# 1_P1.net
KiCad netlist of a schematic drawn in Altium Designer
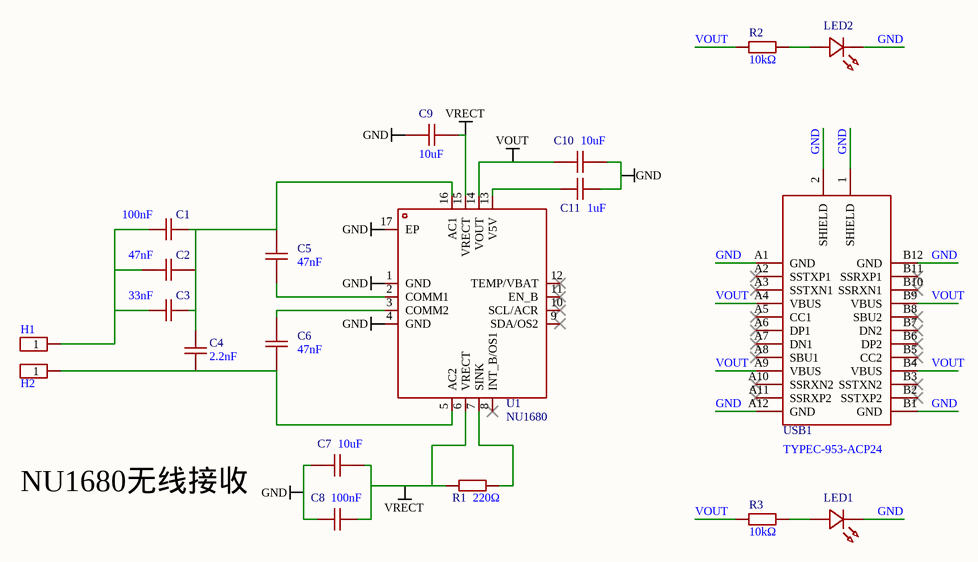
[diagram p0: 1_P1.schdoc]

(export (version "E")
  (design (tool "Eeschema 10.0.6"))
  (components
    (comp (ref "C1")
      (value "100nF")
      (footprint "C0603")
      (fields
        (field (name "MANUFACTURER") "FH(风华)")
        (field (name "MANUFACTURER PART") "0603B104K500NT")
        (field (name "TOLERANCE") "±10%")
      )
      (libsource (lib "altium-import") (part "root_0_0603B104K500NT_"))
    )
    (comp (ref "C2")
      (value "47nF")
      (footprint "C0603")
      (fields
        (field (name "MANUFACTURER") "FH(风华)")
        (field (name "MANUFACTURER PART") "0603B473K500NT")
        (field (name "TOLERANCE") "±10%")
      )
      (libsource (lib "altium-import") (part "root_1_0603B473K500NT_"))
    )
    (comp (ref "C3")
      (value "33nF")
      (footprint "C0603")
      (fields
        (field (name "MANUFACTURER") "SAMSUNG(三星)")
        (field (name "MANUFACTURER PART") "CL10B333KB8NNNC")
        (field (name "TOLERANCE") "±10%")
      )
      (libsource (lib "altium-import") (part "root_0_CL10B333KB8NNNC_"))
    )
    (comp (ref "C4")
      (value "2.2nF")
      (footprint "C0603")
      (fields
        (field (name "MANUFACTURER") "FH(风华)")
        (field (name "MANUFACTURER PART") "0603B222K500NT")
        (field (name "TOLERANCE") "±10%")
      )
      (libsource (lib "altium-import") (part "root_1_0603B222K500NT_"))
    )
    (comp (ref "C5")
      (value "47nF")
      (footprint "C0603")
      (fields
        (field (name "MANUFACTURER") "FH(风华)")
        (field (name "MANUFACTURER PART") "0603B473K500NT")
        (field (name "TOLERANCE") "±10%")
      )
      (libsource (lib "altium-import") (part "root_2_0603B473K500NT_"))
    )
    (comp (ref "C6")
      (value "47nF")
      (footprint "C0603")
      (fields
        (field (name "MANUFACTURER") "FH(风华)")
        (field (name "MANUFACTURER PART") "0603B473K500NT")
        (field (name "TOLERANCE") "±10%")
      )
      (libsource (lib "altium-import") (part "root_2_0603B473K500NT_"))
    )
    (comp (ref "C7")
      (value "10uF")
      (footprint "C0603")
      (fields
        (field (name "MANUFACTURER") "SAMSUNG(三星)")
        (field (name "MANUFACTURER PART") "CL10A106MA8NRNC")
        (field (name "TOLERANCE") "±20%")
      )
      (libsource (lib "altium-import") (part "root_0_CL10A106MA8NRNC_"))
    )
    (comp (ref "C8")
      (value "100nF")
      (footprint "C0603")
      (fields
        (field (name "MANUFACTURER") "FH(风华)")
        (field (name "MANUFACTURER PART") "0603B104K500NT")
        (field (name "TOLERANCE") "±10%")
      )
      (libsource (lib "altium-import") (part "root_0_0603B104K500NT_"))
    )
    (comp (ref "C9")
      (value "10uF")
      (footprint "C0603")
      (fields
        (field (name "MANUFACTURER") "SAMSUNG(三星)")
        (field (name "MANUFACTURER PART") "CL10A106MA8NRNC")
        (field (name "TOLERANCE") "±20%")
      )
      (libsource (lib "altium-import") (part "root_0_CL10A106MA8NRNC_"))
    )
    (comp (ref "C10")
      (value "10uF")
      (footprint "C0603")
      (fields
        (field (name "MANUFACTURER") "SAMSUNG(三星)")
        (field (name "MANUFACTURER PART") "CL10A106MA8NRNC")
        (field (name "TOLERANCE") "±20%")
      )
      (libsource (lib "altium-import") (part "root_0_CL10A106MA8NRNC_"))
    )
    (comp (ref "C11")
      (value "1uF")
      (footprint "C0603")
      (fields
        (field (name "MANUFACTURER PART") "CL10A105KB8NNNC")
        (field (name "MANUFACTURER") "SAMSUNG(三星)")
        (field (name "TOLERANCE") "±10%")
      )
      (libsource (lib "altium-import") (part "root_0_CL10A105KB8NNNC_"))
    )
    (comp (ref "H1")
      (value "2.54-1*1P针")
      (footprint "2mm-1.3mm孔")
      (fields (field (name "MANUFACTURER") "BOOMELE(博穆精密)"))
      (libsource (lib "altium-import") (part "root_2_2.54-1*1P针_"))
    )
    (comp (ref "H2")
      (value "2.54-1*1P针")
      (footprint "2mm-1.3mm孔")
      (fields (field (name "MANUFACTURER") "BOOMELE(博穆精密)"))
      (libsource (lib "altium-import") (part "root_2_2.54-1*1P针_"))
    )
    (comp (ref "LED1")
      (value "MHT192DUGCT")
      (footprint "LED0603-RD")
      (fields (field (name "MANUFACTURER") "MEIHUA(美华)"))
      (libsource (lib "altium-import") (part "root_2_MHT192DUGCT_"))
    )
    (comp (ref "LED2")
      (value "MHT192DUGCT")
      (footprint "LED0603-RD")
      (fields (field (name "MANUFACTURER") "MEIHUA(美华)"))
      (libsource (lib "altium-import") (part "root_2_MHT192DUGCT_"))
    )
    (comp (ref "R1")
      (value "220Ω")
      (footprint "R0805")
      (fields
        (field (name "MANUFACTURER") "UNI-ROYAL(厚声)")
        (field (name "MANUFACTURER PART") "0805W8J0221T5E")
        (field (name "TOLERANCE") "±5%")
      )
      (libsource (lib "altium-import") (part "root_0_0805W8J0221T5E_"))
    )
    (comp (ref "R2")
      (value "10kΩ")
      (footprint "R0603")
      (fields
        (field (name "MANUFACTURER") "UNI-ROYAL(厚声)")
        (field (name "MANUFACTURER PART") "0603WAF1002T5E")
        (field (name "TOLERANCE") "±1%")
      )
      (libsource (lib "altium-import") (part "root_0_0603WAF1002T5E_"))
    )
    (comp (ref "R3")
      (value "10kΩ")
      (footprint "R0603")
      (fields
        (field (name "MANUFACTURER") "UNI-ROYAL(厚声)")
        (field (name "MANUFACTURER PART") "0603WAF1002T5E")
        (field (name "TOLERANCE") "±1%")
      )
      (libsource (lib "altium-import") (part "root_0_0603WAF1002T5E_"))
    )
    (comp (ref "U1")
      (value "NU1680")
      (footprint "QFN-16_L3.0-W3.0-P0.50-TL-EP1.9")
      (fields (field (name "DEVICE") "NU1680"))
      (libsource (lib "altium-import") (part "root_0_NU1680_"))
    )
    (comp (ref "USB1")
      (value "TYPEC-953-ACP24")
      (footprint "USB-C-SMD_TYPEC-953-ACP24")
      (fields (field (name "MANUFACTURER") "XUNPU(讯普)"))
      (libsource (lib "altium-import") (part "root_0_TYPEC-953-ACP24_"))
    )
  )
  (nets
    (net (code "1") (name "GND") (class "Default")
      (node (ref "C10") (pin "2") (pinfunction "2_2") (pintype "passive"))
      (node (ref "C11") (pin "2") (pinfunction "2_2") (pintype "passive"))
      (node (ref "C7") (pin "1") (pinfunction "1_1") (pintype "passive"))
      (node (ref "C8") (pin "1") (pinfunction "1_1") (pintype "passive"))
      (node (ref "C9") (pin "1") (pinfunction "1_1") (pintype "passive"))
      (node (ref "LED1") (pin "1") (pinfunction "K_1") (pintype "passive"))
      (node (ref "LED2") (pin "1") (pinfunction "K_1") (pintype "passive"))
      (node (ref "U1") (pin "1") (pinfunction "GND_1") (pintype "passive"))
      (node (ref "U1") (pin "17") (pinfunction "EP_17") (pintype "passive"))
      (node (ref "U1") (pin "4") (pinfunction "GND_4") (pintype "passive"))
      (node (ref "USB1") (pin "1") (pinfunction "SHIELD_1") (pintype "passive"))
      (node (ref "USB1") (pin "2") (pinfunction "SHIELD_2") (pintype "passive"))
      (node (ref "USB1") (pin "A1") (pinfunction "GND_A1") (pintype "passive"))
      (node (ref "USB1") (pin "A12") (pinfunction "GND_A12") (pintype "passive"))
      (node (ref "USB1") (pin "B1") (pinfunction "GND_B1") (pintype "passive"))
      (node (ref "USB1") (pin "B12") (pinfunction "GND_B12") (pintype "passive"))
    )
    (net (code "2") (name "Net-(C1-Pad1)") (class "Default")
      (node (ref "C1") (pin "1") (pinfunction "1_1") (pintype "passive"))
      (node (ref "C2") (pin "2") (pinfunction "2_2") (pintype "passive"))
      (node (ref "C3") (pin "1") (pinfunction "1_1") (pintype "passive"))
      (node (ref "H1") (pin "1") (pinfunction "1_1") (pintype "passive"))
    )
    (net (code "3") (name "Net-(LED1-A)") (class "Default")
      (node (ref "LED1") (pin "2") (pinfunction "A_2") (pintype "passive"))
      (node (ref "R3") (pin "2") (pinfunction "2_2") (pintype "passive"))
    )
    (net (code "4") (name "Net-(LED2-A)") (class "Default")
      (node (ref "LED2") (pin "2") (pinfunction "A_2") (pintype "passive"))
      (node (ref "R2") (pin "2") (pinfunction "2_2") (pintype "passive"))
    )
    (net (code "5") (name "Net-(U1-AC1)") (class "Default")
      (node (ref "C1") (pin "2") (pinfunction "2_2") (pintype "passive"))
      (node (ref "C2") (pin "1") (pinfunction "1_1") (pintype "passive"))
      (node (ref "C3") (pin "2") (pinfunction "2_2") (pintype "passive"))
      (node (ref "C4") (pin "2") (pinfunction "2_2") (pintype "passive"))
      (node (ref "C5") (pin "1") (pinfunction "1_1") (pintype "passive"))
      (node (ref "U1") (pin "16") (pinfunction "AC1_16") (pintype "passive"))
    )
    (net (code "6") (name "Net-(U1-AC2)") (class "Default")
      (node (ref "C4") (pin "1") (pinfunction "1_1") (pintype "passive"))
      (node (ref "C6") (pin "2") (pinfunction "2_2") (pintype "passive"))
      (node (ref "H2") (pin "1") (pinfunction "1_1") (pintype "passive"))
      (node (ref "U1") (pin "5") (pinfunction "AC2_5") (pintype "passive"))
    )
    (net (code "7") (name "Net-(U1-COMM1)") (class "Default")
      (node (ref "C5") (pin "2") (pinfunction "2_2") (pintype "passive"))
      (node (ref "U1") (pin "2") (pinfunction "COMM1_2") (pintype "passive"))
    )
    (net (code "8") (name "Net-(U1-COMM2)") (class "Default")
      (node (ref "C6") (pin "1") (pinfunction "1_1") (pintype "passive"))
      (node (ref "U1") (pin "3") (pinfunction "COMM2_3") (pintype "passive"))
    )
    (net (code "9") (name "Net-(U1-SINK)") (class "Default")
      (node (ref "R1") (pin "2") (pinfunction "2_2") (pintype "passive"))
      (node (ref "U1") (pin "7") (pinfunction "SINK_7") (pintype "passive"))
    )
    (net (code "10") (name "Net-(U1-V5V)") (class "Default")
      (node (ref "C11") (pin "1") (pinfunction "1_1") (pintype "passive"))
      (node (ref "U1") (pin "13") (pinfunction "V5V_13") (pintype "passive"))
    )
    (net (code "11") (name "VOUT") (class "Default")
      (node (ref "C10") (pin "1") (pinfunction "1_1") (pintype "passive"))
      (node (ref "R2") (pin "1") (pinfunction "1_1") (pintype "passive"))
      (node (ref "R3") (pin "1") (pinfunction "1_1") (pintype "passive"))
      (node (ref "U1") (pin "14") (pinfunction "VOUT_14") (pintype "passive"))
      (node (ref "USB1") (pin "A4") (pinfunction "VBUS_A4") (pintype "passive"))
      (node (ref "USB1") (pin "A9") (pinfunction "VBUS_A9") (pintype "passive"))
      (node (ref "USB1") (pin "B4") (pinfunction "VBUS_B4") (pintype "passive"))
      (node (ref "USB1") (pin "B9") (pinfunction "VBUS_B9") (pintype "passive"))
    )
    (net (code "12") (name "VRECT") (class "Default")
      (node (ref "C7") (pin "2") (pinfunction "2_2") (pintype "passive"))
      (node (ref "C8") (pin "2") (pinfunction "2_2") (pintype "passive"))
      (node (ref "C9") (pin "2") (pinfunction "2_2") (pintype "passive"))
      (node (ref "R1") (pin "1") (pinfunction "1_1") (pintype "passive"))
      (node (ref "U1") (pin "15") (pinfunction "VRECT_15") (pintype "passive"))
      (node (ref "U1") (pin "6") (pinfunction "VRECT_6") (pintype "passive"))
    )
    (net (code "13") (name "unconnected-(U1-EN_B-Pad11)") (class "Default")
      (node (ref "U1") (pin "11") (pinfunction "EN_B_11") (pintype "passive+no_connect"))
    )
    (net (code "14") (name "unconnected-(U1-INT_B{slash}OS1-Pad8)") (class "Default")
      (node (ref "U1") (pin "8") (pinfunction "INT_B/OS1_8") (pintype "passive+no_connect"))
    )
    (net (code "15") (name "unconnected-(U1-SCL{slash}ACR-Pad10)") (class "Default")
      (node (ref "U1") (pin "10") (pinfunction "SCL/ACR_10") (pintype "passive+no_connect"))
    )
    (net (code "16") (name "unconnected-(U1-SDA{slash}OS2-Pad9)") (class "Default")
      (node (ref "U1") (pin "9") (pinfunction "SDA/OS2_9") (pintype "passive+no_connect"))
    )
    (net (code "17") (name "unconnected-(U1-TEMP{slash}VBAT-Pad12)") (class "Default")
      (node (ref "U1") (pin "12") (pinfunction "TEMP/VBAT_12") (pintype "passive+no_connect"))
    )
    (net (code "18") (name "unconnected-(USB1-CC1-PadA5)") (class "Default")
      (node (ref "USB1") (pin "A5") (pinfunction "CC1_A5") (pintype "passive+no_connect"))
    )
    (net (code "19") (name "unconnected-(USB1-CC2-PadB5)") (class "Default")
      (node (ref "USB1") (pin "B5") (pinfunction "CC2_B5") (pintype "passive+no_connect"))
    )
    (net (code "20") (name "unconnected-(USB1-DN1-PadA7)") (class "Default")
      (node (ref "USB1") (pin "A7") (pinfunction "DN1_A7") (pintype "passive+no_connect"))
    )
    (net (code "21") (name "unconnected-(USB1-DN2-PadB7)") (class "Default")
      (node (ref "USB1") (pin "B7") (pinfunction "DN2_B7") (pintype "passive+no_connect"))
    )
    (net (code "22") (name "unconnected-(USB1-DP1-PadA6)") (class "Default")
      (node (ref "USB1") (pin "A6") (pinfunction "DP1_A6") (pintype "passive+no_connect"))
    )
    (net (code "23") (name "unconnected-(USB1-DP2-PadB6)") (class "Default")
      (node (ref "USB1") (pin "B6") (pinfunction "DP2_B6") (pintype "passive+no_connect"))
    )
    (net (code "24") (name "unconnected-(USB1-SBU1-PadA8)") (class "Default")
      (node (ref "USB1") (pin "A8") (pinfunction "SBU1_A8") (pintype "passive+no_connect"))
    )
    (net (code "25") (name "unconnected-(USB1-SBU2-PadB8)") (class "Default")
      (node (ref "USB1") (pin "B8") (pinfunction "SBU2_B8") (pintype "passive+no_connect"))
    )
    (net (code "26") (name "unconnected-(USB1-SSRXN1-PadB10)") (class "Default")
      (node (ref "USB1") (pin "B10") (pinfunction "SSRXN1_B10") (pintype "passive+no_connect"))
    )
    (net (code "27") (name "unconnected-(USB1-SSRXN2-PadA10)") (class "Default")
      (node (ref "USB1") (pin "A10") (pinfunction "SSRXN2_A10") (pintype "passive+no_connect"))
    )
    (net (code "28") (name "unconnected-(USB1-SSRXP1-PadB11)") (class "Default")
      (node (ref "USB1") (pin "B11") (pinfunction "SSRXP1_B11") (pintype "passive+no_connect"))
    )
    (net (code "29") (name "unconnected-(USB1-SSRXP2-PadA11)") (class "Default")
      (node (ref "USB1") (pin "A11") (pinfunction "SSRXP2_A11") (pintype "passive+no_connect"))
    )
    (net (code "30") (name "unconnected-(USB1-SSTXN1-PadA3)") (class "Default")
      (node (ref "USB1") (pin "A3") (pinfunction "SSTXN1_A3") (pintype "passive+no_connect"))
    )
    (net (code "31") (name "unconnected-(USB1-SSTXN2-PadB3)") (class "Default")
      (node (ref "USB1") (pin "B3") (pinfunction "SSTXN2_B3") (pintype "passive+no_connect"))
    )
    (net (code "32") (name "unconnected-(USB1-SSTXP1-PadA2)") (class "Default")
      (node (ref "USB1") (pin "A2") (pinfunction "SSTXP1_A2") (pintype "passive+no_connect"))
    )
    (net (code "33") (name "unconnected-(USB1-SSTXP2-PadB2)") (class "Default")
      (node (ref "USB1") (pin "B2") (pinfunction "SSTXP2_B2") (pintype "passive+no_connect"))
    )
  )
)
